# Untitled.net
KiCad netlist of a schematic drawn in EAGLE
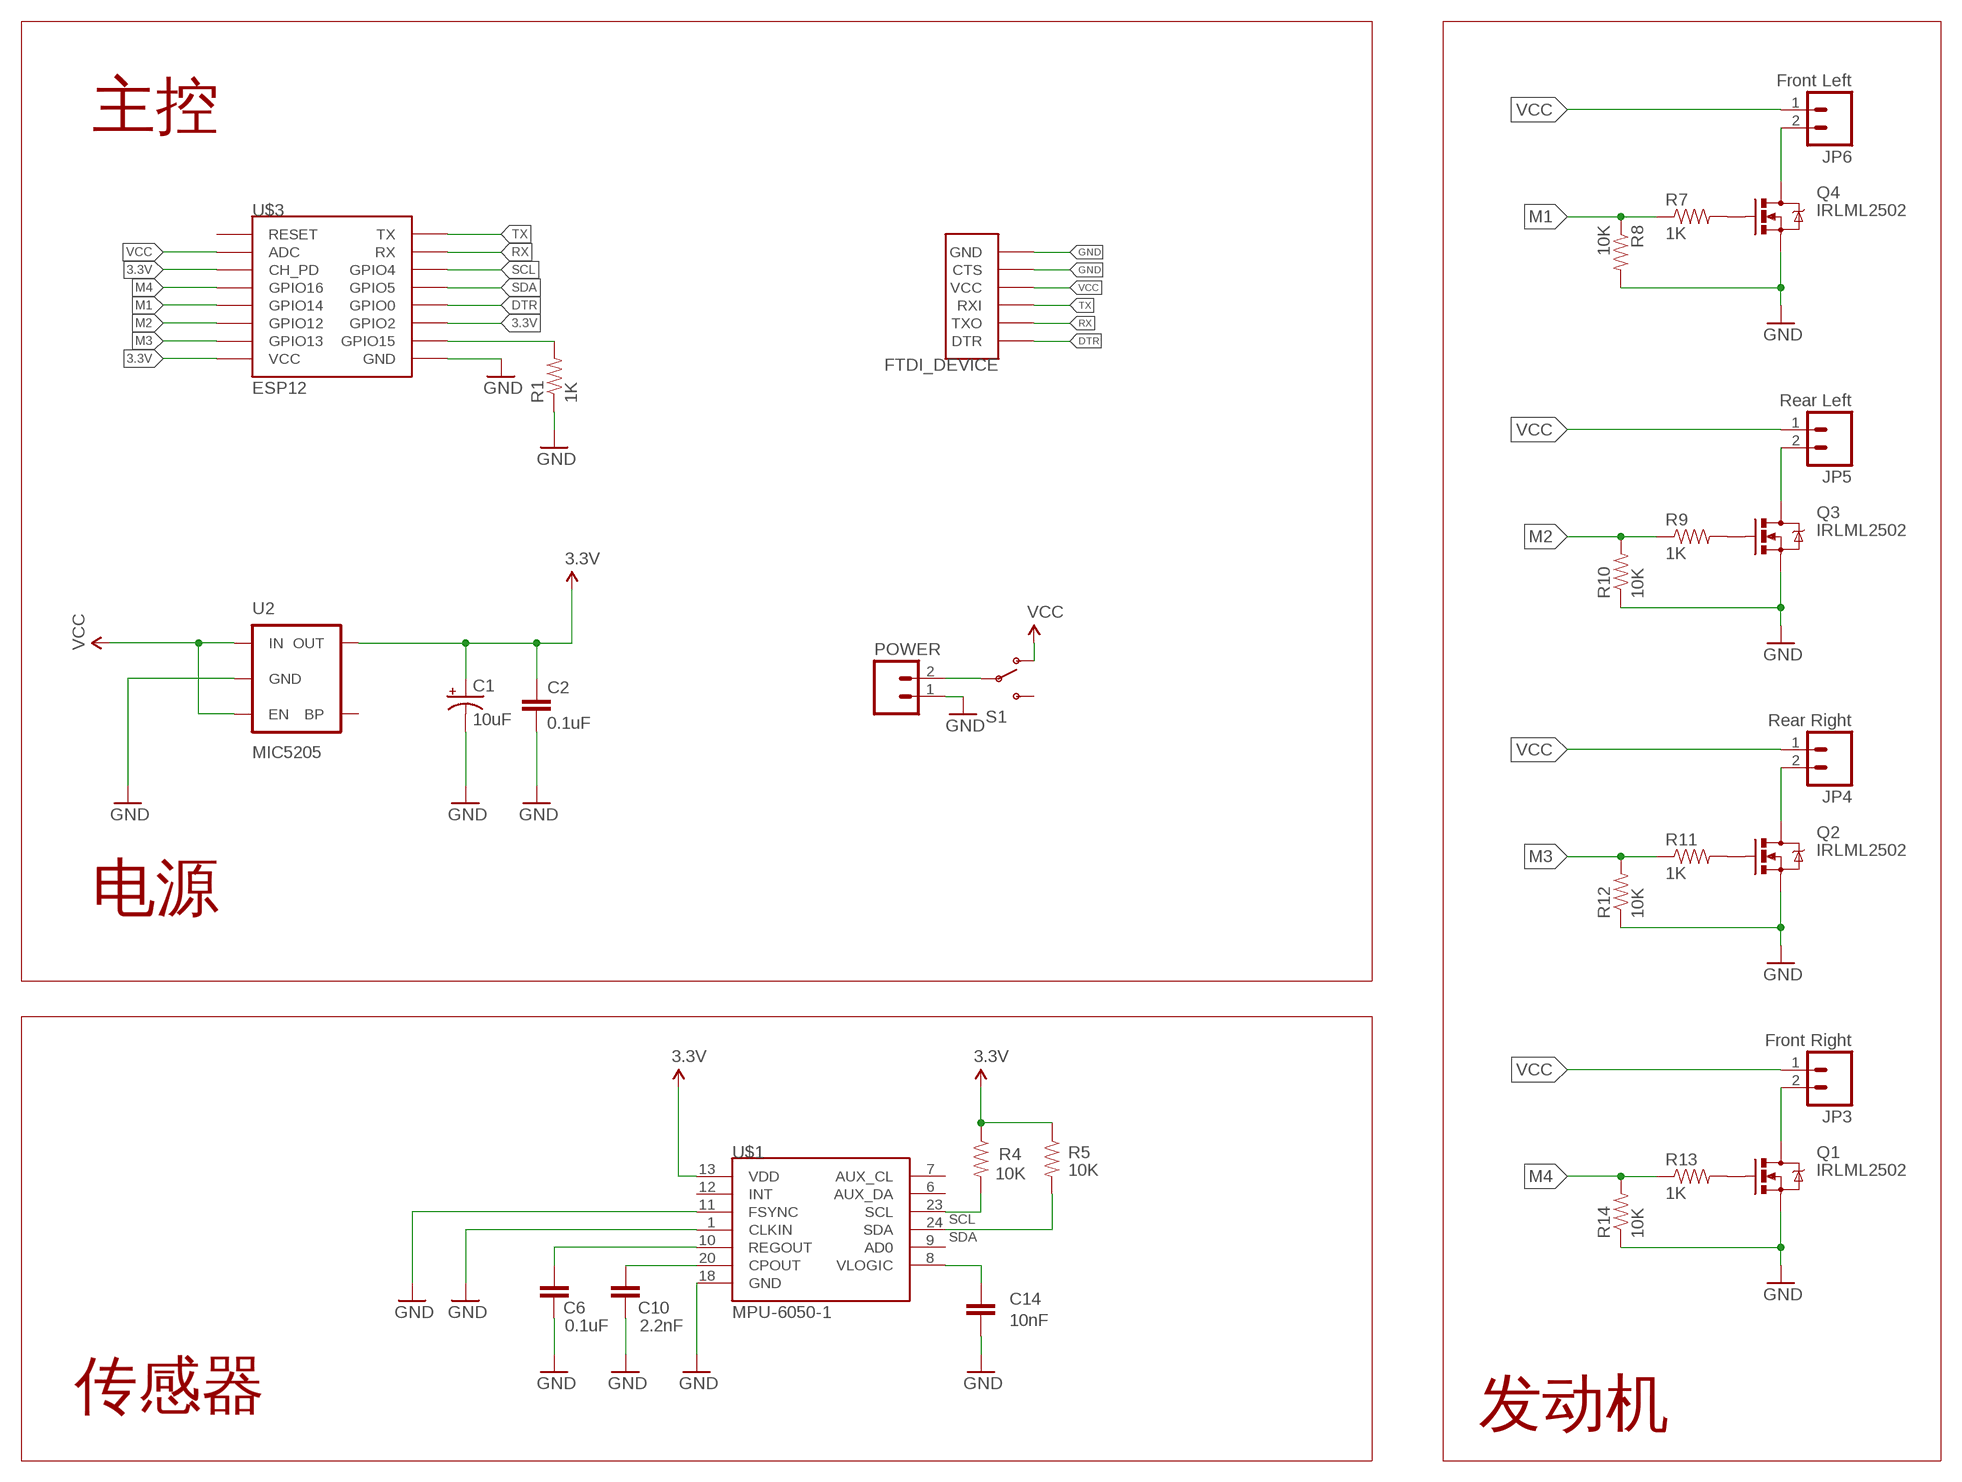
[diagram p0: schematic, sheet 1]

(export (version "E")
  (design (tool "Eeschema 10.0.6"))
  (components
    (comp (ref "C1")
      (value "10uF")
      (footprint "eagle-import:EIA3216")
      (libsource (lib "eagle-import") (part "CAP_POL1206"))
    )
    (comp (ref "C2")
      (value "0.1uF")
      (footprint "eagle-import:0402-CAP")
      (libsource (lib "eagle-import") (part "CAP0402-CAP"))
    )
    (comp (ref "C6")
      (value "0.1uF")
      (footprint "eagle-import:0402-CAP")
      (libsource (lib "eagle-import") (part "CAP0402-CAP"))
    )
    (comp (ref "C10")
      (value "2.2nF")
      (footprint "eagle-import:0402-CAP")
      (libsource (lib "eagle-import") (part "CAP0402-CAP"))
    )
    (comp (ref "C14")
      (value "10nF")
      (footprint "eagle-import:0402-CAP")
      (libsource (lib "eagle-import") (part "CAP0402-CAP"))
    )
    (comp (ref "FTDI")
      (value "FTDI_DEVICE")
      (footprint "eagle-import:FTDI_DEVICE_SIDE")
      (libsource (lib "eagle-import") (part "FTDI_DEVICE"))
    )
    (comp (ref "JP3")
      (value "Front Right")
      (footprint "eagle-import:1X02_LONGPADS")
      (libsource (lib "eagle-import") (part "M02PTH3"))
    )
    (comp (ref "JP4")
      (value "Rear Right")
      (footprint "eagle-import:1X02_LONGPADS")
      (libsource (lib "eagle-import") (part "M02PTH3"))
    )
    (comp (ref "JP5")
      (value "Rear Left")
      (footprint "eagle-import:1X02_LONGPADS")
      (libsource (lib "eagle-import") (part "M02PTH3"))
    )
    (comp (ref "JP6")
      (value "Front Left")
      (footprint "eagle-import:1X02_LONGPADS")
      (libsource (lib "eagle-import") (part "M02PTH3"))
    )
    (comp (ref "POWER")
      (value "M02PTH")
      (footprint "eagle-import:1X02")
      (libsource (lib "eagle-import") (part "M02PTH"))
    )
    (comp (ref "Q1")
      (value "IRLML2502")
      (footprint "eagle-import:SOT23")
      (libsource (lib "eagle-import") (part "MOSFET-NCHANNELBSS138"))
    )
    (comp (ref "Q2")
      (value "IRLML2502")
      (footprint "eagle-import:SOT23")
      (libsource (lib "eagle-import") (part "MOSFET-NCHANNELBSS138"))
    )
    (comp (ref "Q3")
      (value "IRLML2502")
      (footprint "eagle-import:SOT23")
      (libsource (lib "eagle-import") (part "MOSFET-NCHANNELBSS138"))
    )
    (comp (ref "Q4")
      (value "IRLML2502")
      (footprint "eagle-import:SOT23")
      (libsource (lib "eagle-import") (part "MOSFET-NCHANNELBSS138"))
    )
    (comp (ref "R1")
      (value "1K")
      (footprint "eagle-import:0402-RES")
      (libsource (lib "eagle-import") (part "RESISTOR0402-RES"))
    )
    (comp (ref "R4")
      (value "10K")
      (footprint "eagle-import:0402-RES")
      (libsource (lib "eagle-import") (part "RESISTOR0402-RES"))
    )
    (comp (ref "R5")
      (value "10K")
      (footprint "eagle-import:0402-RES")
      (libsource (lib "eagle-import") (part "RESISTOR0402-RES"))
    )
    (comp (ref "R7")
      (value "1K")
      (footprint "eagle-import:0402-RES")
      (libsource (lib "eagle-import") (part "RESISTOR0402-RES"))
    )
    (comp (ref "R8")
      (value "10K")
      (footprint "eagle-import:0402-RES")
      (libsource (lib "eagle-import") (part "RESISTOR0402-RES"))
    )
    (comp (ref "R9")
      (value "1K")
      (footprint "eagle-import:0402-RES")
      (libsource (lib "eagle-import") (part "RESISTOR0402-RES"))
    )
    (comp (ref "R10")
      (value "10K")
      (footprint "eagle-import:0402-RES")
      (libsource (lib "eagle-import") (part "RESISTOR0402-RES"))
    )
    (comp (ref "R11")
      (value "1K")
      (footprint "eagle-import:0402-RES")
      (libsource (lib "eagle-import") (part "RESISTOR0402-RES"))
    )
    (comp (ref "R12")
      (value "10K")
      (footprint "eagle-import:0402-RES")
      (libsource (lib "eagle-import") (part "RESISTOR0402-RES"))
    )
    (comp (ref "R13")
      (value "1K")
      (footprint "eagle-import:0402-RES")
      (libsource (lib "eagle-import") (part "RESISTOR0402-RES"))
    )
    (comp (ref "R14")
      (value "10K")
      (footprint "eagle-import:0402-RES")
      (libsource (lib "eagle-import") (part "RESISTOR0402-RES"))
    )
    (comp (ref "S1")
      (value "SWITCH-SPDTSMD2")
      (footprint "eagle-import:SWITCH-SPDT-SMD")
      (libsource (lib "eagle-import") (part "SWITCH-SPDTSMD2"))
    )
    (comp (ref "U$1")
      (value "MPU-6050-1")
      (footprint "eagle-import:QFN-24-4MM2")
      (libsource (lib "eagle-import") (part "MPU-6050-1"))
    )
    (comp (ref "U$3")
      (value "ESP12")
      (footprint "eagle-import:ESP12")
      (libsource (lib "eagle-import") (part "ESP12"))
    )
    (comp (ref "U2")
      (value "MIC5205")
      (footprint "eagle-import:SOT23-5")
      (libsource (lib "eagle-import") (part "MIC52055V"))
    )
  )
  (nets
    (net (code "1") (name "3.3V") (class "Default")
      (node (ref "C1") (pin "A") (pinfunction "+_A") (pintype "passive"))
      (node (ref "C2") (pin "1") (pinfunction "1_1") (pintype "passive"))
      (node (ref "R4") (pin "1") (pinfunction "1_1") (pintype "passive"))
      (node (ref "R5") (pin "1") (pinfunction "1_1") (pintype "passive"))
      (node (ref "U$1") (pin "13") (pinfunction "VDD_13") (pintype "bidirectional"))
      (node (ref "U$3") (pin "CH_PD") (pinfunction "CH_PD_CH_PD") (pintype "bidirectional"))
      (node (ref "U$3") (pin "GPIO2") (pinfunction "GPIO2_GPIO2") (pintype "bidirectional"))
      (node (ref "U$3") (pin "VCC") (pinfunction "VCC_VCC") (pintype "bidirectional"))
      (node (ref "U2") (pin "5") (pinfunction "OUT_5") (pintype "passive"))
    )
    (net (code "2") (name "DTR") (class "Default")
      (node (ref "FTDI") (pin "P$1") (pinfunction "DTR_P$1") (pintype "bidirectional"))
      (node (ref "U$3") (pin "GPIO0") (pinfunction "GPIO0_GPIO0") (pintype "bidirectional"))
    )
    (net (code "3") (name "GND") (class "Default")
      (node (ref "C1") (pin "C") (pinfunction "-_C") (pintype "passive"))
      (node (ref "C10") (pin "1") (pinfunction "1_1") (pintype "passive"))
      (node (ref "C14") (pin "1") (pinfunction "1_1") (pintype "passive"))
      (node (ref "C2") (pin "2") (pinfunction "2_2") (pintype "passive"))
      (node (ref "C6") (pin "1") (pinfunction "1_1") (pintype "passive"))
      (node (ref "FTDI") (pin "P$5") (pinfunction "CTS_P$5") (pintype "bidirectional"))
      (node (ref "FTDI") (pin "P$6") (pinfunction "GND_P$6") (pintype "bidirectional"))
      (node (ref "POWER") (pin "1") (pinfunction "1_1") (pintype "passive"))
      (node (ref "Q1") (pin "2") (pinfunction "S_2") (pintype "passive"))
      (node (ref "Q2") (pin "2") (pinfunction "S_2") (pintype "passive"))
      (node (ref "Q3") (pin "2") (pinfunction "S_2") (pintype "passive"))
      (node (ref "Q4") (pin "2") (pinfunction "S_2") (pintype "passive"))
      (node (ref "R1") (pin "1") (pinfunction "1_1") (pintype "passive"))
      (node (ref "R10") (pin "1") (pinfunction "1_1") (pintype "passive"))
      (node (ref "R12") (pin "1") (pinfunction "1_1") (pintype "passive"))
      (node (ref "R14") (pin "1") (pinfunction "1_1") (pintype "passive"))
      (node (ref "R8") (pin "2") (pinfunction "2_2") (pintype "passive"))
      (node (ref "U$1") (pin "1") (pinfunction "CLKIN_1") (pintype "bidirectional"))
      (node (ref "U$1") (pin "11") (pinfunction "FSYNC_11") (pintype "bidirectional"))
      (node (ref "U$1") (pin "18") (pinfunction "GND_18") (pintype "bidirectional"))
      (node (ref "U$3") (pin "GND") (pinfunction "GND_GND") (pintype "bidirectional"))
      (node (ref "U2") (pin "2") (pinfunction "GND_2") (pintype "input"))
    )
    (net (code "4") (name "M1") (class "Default")
      (node (ref "R7") (pin "1") (pinfunction "1_1") (pintype "passive"))
      (node (ref "R8") (pin "1") (pinfunction "1_1") (pintype "passive"))
      (node (ref "U$3") (pin "GPIO14") (pinfunction "GPIO14_GPIO14") (pintype "bidirectional"))
    )
    (net (code "5") (name "M2") (class "Default")
      (node (ref "R10") (pin "2") (pinfunction "2_2") (pintype "passive"))
      (node (ref "R9") (pin "1") (pinfunction "1_1") (pintype "passive"))
      (node (ref "U$3") (pin "GPIO12") (pinfunction "GPIO12_GPIO12") (pintype "bidirectional"))
    )
    (net (code "6") (name "M3") (class "Default")
      (node (ref "R11") (pin "1") (pinfunction "1_1") (pintype "passive"))
      (node (ref "R12") (pin "2") (pinfunction "2_2") (pintype "passive"))
      (node (ref "U$3") (pin "GPIO13") (pinfunction "GPIO13_GPIO13") (pintype "bidirectional"))
    )
    (net (code "7") (name "M4") (class "Default")
      (node (ref "R13") (pin "1") (pinfunction "1_1") (pintype "passive"))
      (node (ref "R14") (pin "2") (pinfunction "2_2") (pintype "passive"))
      (node (ref "U$3") (pin "GPIO16") (pinfunction "GPIO16_GPIO16") (pintype "bidirectional"))
    )
    (net (code "8") (name "Net-(Q1-D)") (class "Default")
      (node (ref "JP3") (pin "2") (pinfunction "2_2") (pintype "passive"))
      (node (ref "Q1") (pin "3") (pinfunction "D_3") (pintype "passive"))
    )
    (net (code "9") (name "Net-(Q1-G)") (class "Default")
      (node (ref "Q1") (pin "1") (pinfunction "G_1") (pintype "passive"))
      (node (ref "R13") (pin "2") (pinfunction "2_2") (pintype "passive"))
    )
    (net (code "10") (name "Net-(Q2-D)") (class "Default")
      (node (ref "JP4") (pin "2") (pinfunction "2_2") (pintype "passive"))
      (node (ref "Q2") (pin "3") (pinfunction "D_3") (pintype "passive"))
    )
    (net (code "11") (name "Net-(Q2-G)") (class "Default")
      (node (ref "Q2") (pin "1") (pinfunction "G_1") (pintype "passive"))
      (node (ref "R11") (pin "2") (pinfunction "2_2") (pintype "passive"))
    )
    (net (code "12") (name "Net-(Q3-D)") (class "Default")
      (node (ref "JP5") (pin "2") (pinfunction "2_2") (pintype "passive"))
      (node (ref "Q3") (pin "3") (pinfunction "D_3") (pintype "passive"))
    )
    (net (code "13") (name "Net-(Q3-G)") (class "Default")
      (node (ref "Q3") (pin "1") (pinfunction "G_1") (pintype "passive"))
      (node (ref "R9") (pin "2") (pinfunction "2_2") (pintype "passive"))
    )
    (net (code "14") (name "Net-(Q4-D)") (class "Default")
      (node (ref "JP6") (pin "2") (pinfunction "2_2") (pintype "passive"))
      (node (ref "Q4") (pin "3") (pinfunction "D_3") (pintype "passive"))
    )
    (net (code "15") (name "Net-(Q4-G)") (class "Default")
      (node (ref "Q4") (pin "1") (pinfunction "G_1") (pintype "passive"))
      (node (ref "R7") (pin "2") (pinfunction "2_2") (pintype "passive"))
    )
    (net (code "16") (name "Net-(R1-Pad2)") (class "Default")
      (node (ref "R1") (pin "2") (pinfunction "2_2") (pintype "passive"))
      (node (ref "U$3") (pin "GPIO15") (pinfunction "GPIO15_GPIO15") (pintype "bidirectional"))
    )
    (net (code "17") (name "Net-(S1-P)") (class "Default")
      (node (ref "POWER") (pin "2") (pinfunction "2_2") (pintype "passive"))
      (node (ref "S1") (pin "2") (pinfunction "P_2") (pintype "passive"))
    )
    (net (code "18") (name "Net-(U$1-CPOUT)") (class "Default")
      (node (ref "C10") (pin "2") (pinfunction "2_2") (pintype "passive"))
      (node (ref "U$1") (pin "20") (pinfunction "CPOUT_20") (pintype "bidirectional"))
    )
    (net (code "19") (name "Net-(U$1-REGOUT)") (class "Default")
      (node (ref "C6") (pin "2") (pinfunction "2_2") (pintype "passive"))
      (node (ref "U$1") (pin "10") (pinfunction "REGOUT_10") (pintype "bidirectional"))
    )
    (net (code "20") (name "Net-(U$1-VLOGIC)") (class "Default")
      (node (ref "C14") (pin "2") (pinfunction "2_2") (pintype "passive"))
      (node (ref "U$1") (pin "8") (pinfunction "VLOGIC_8") (pintype "bidirectional"))
    )
    (net (code "21") (name "RX") (class "Default")
      (node (ref "FTDI") (pin "P$2") (pinfunction "TXO_P$2") (pintype "bidirectional"))
      (node (ref "U$3") (pin "RX") (pinfunction "RX_RX") (pintype "bidirectional"))
    )
    (net (code "22") (name "SCL") (class "Default")
      (node (ref "R4") (pin "2") (pinfunction "2_2") (pintype "passive"))
      (node (ref "U$1") (pin "23") (pinfunction "SCL_23") (pintype "bidirectional"))
      (node (ref "U$3") (pin "GPIO4") (pinfunction "GPIO4_GPIO4") (pintype "bidirectional"))
    )
    (net (code "23") (name "SDA") (class "Default")
      (node (ref "R5") (pin "2") (pinfunction "2_2") (pintype "passive"))
      (node (ref "U$1") (pin "24") (pinfunction "SDA_24") (pintype "bidirectional"))
      (node (ref "U$3") (pin "GPIO5") (pinfunction "GPIO5_GPIO5") (pintype "bidirectional"))
    )
    (net (code "24") (name "TX") (class "Default")
      (node (ref "FTDI") (pin "P$3") (pinfunction "RXI_P$3") (pintype "bidirectional"))
      (node (ref "U$3") (pin "TX") (pinfunction "TX_TX") (pintype "bidirectional"))
    )
    (net (code "25") (name "VCC") (class "Default")
      (node (ref "FTDI") (pin "P$4") (pinfunction "VCC_P$4") (pintype "bidirectional"))
      (node (ref "JP3") (pin "1") (pinfunction "1_1") (pintype "passive"))
      (node (ref "JP4") (pin "1") (pinfunction "1_1") (pintype "passive"))
      (node (ref "JP5") (pin "1") (pinfunction "1_1") (pintype "passive"))
      (node (ref "JP6") (pin "1") (pinfunction "1_1") (pintype "passive"))
      (node (ref "S1") (pin "1") (pinfunction "O_1") (pintype "passive"))
      (node (ref "U$3") (pin "ADC") (pinfunction "ADC_ADC") (pintype "bidirectional"))
      (node (ref "U2") (pin "1") (pinfunction "IN_1") (pintype "input"))
      (node (ref "U2") (pin "3") (pinfunction "EN_3") (pintype "input"))
    )
    (net (code "26") (name "unconnected-(S1-S-Pad3)") (class "Default")
      (node (ref "S1") (pin "3") (pinfunction "S_3") (pintype "passive"))
    )
    (net (code "27") (name "unconnected-(U$1-AD0-Pad9)") (class "Default")
      (node (ref "U$1") (pin "9") (pinfunction "AD0_9") (pintype "bidirectional"))
    )
    (net (code "28") (name "unconnected-(U$1-AUX_CL-Pad7)") (class "Default")
      (node (ref "U$1") (pin "7") (pinfunction "AUX_CL_7") (pintype "bidirectional"))
    )
    (net (code "29") (name "unconnected-(U$1-AUX_DA-Pad6)") (class "Default")
      (node (ref "U$1") (pin "6") (pinfunction "AUX_DA_6") (pintype "bidirectional"))
    )
    (net (code "30") (name "unconnected-(U$1-INT-Pad12)") (class "Default")
      (node (ref "U$1") (pin "12") (pinfunction "INT_12") (pintype "bidirectional"))
    )
    (net (code "31") (name "unconnected-(U$3-PadRESET)") (class "Default")
      (node (ref "U$3") (pin "RESET") (pinfunction "RESET_RESET") (pintype "bidirectional"))
    )
    (net (code "32") (name "unconnected-(U2-BP-Pad4)") (class "Default")
      (node (ref "U2") (pin "4") (pinfunction "BP_4") (pintype "input"))
    )
  )
)
